# Sonar.net
KiCad netlist of a schematic drawn in Altium Designer
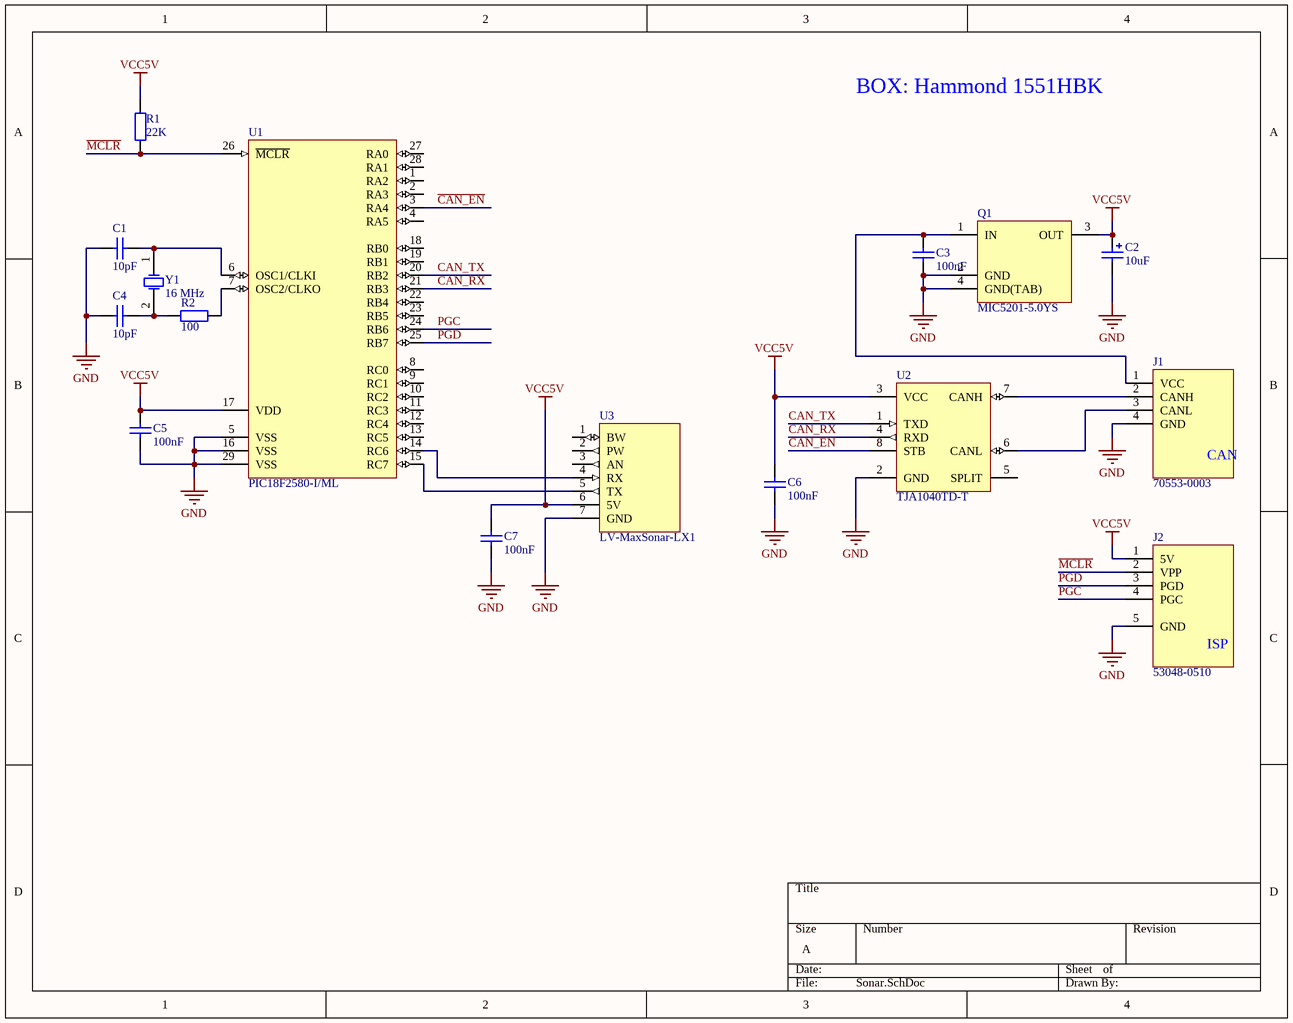
[diagram p0: Sonar.SchDoc]

(export (version "E")
  (design (tool "Eeschema 10.0.6"))
  (components
    (comp (ref "C1")
      (value "10pF")
      (footprint "CC1608-0603")
      (description "Capacitor")
      (fields (field (name "MANUFACTURER") "Panasonic") (field (name "Comment") "Cap"))
      (libsource (lib "Comp") (part "Cap"))
    )
    (comp (ref "C2")
      (value "10uF")
      (footprint "TC3528-1411")
      (description "Polarized Capacitor (Surface Mount)")
      (fields (field (name "MANUFACTURER") "AVX") (field (name "Comment") "TPSB106K016R0800"))
      (libsource (lib "Comp") (part "Cap Pol"))
    )
    (comp (ref "C3")
      (value "100nF")
      (footprint "CC1608-0603")
      (description "Capacitor")
      (fields (field (name "MANUFACTURER") "Taiyo Yuden") (field (name "Comment") "UMK107BJ104KA-T"))
      (libsource (lib "Comp") (part "Cap"))
    )
    (comp (ref "C4")
      (value "10pF")
      (footprint "CC1608-0603")
      (description "Capacitor")
      (fields (field (name "MANUFACTURER") "Panasonic") (field (name "Comment") "Cap"))
      (libsource (lib "Comp") (part "Cap"))
    )
    (comp (ref "C5")
      (value "100nF")
      (footprint "CC1608-0603")
      (description "Capacitor")
      (fields (field (name "MANUFACTURER") "Taiyo Yuden") (field (name "Comment") "UMK107BJ104KA-T"))
      (libsource (lib "Comp") (part "Cap"))
    )
    (comp (ref "C6")
      (value "100nF")
      (footprint "CC1608-0603")
      (description "Capacitor")
      (fields (field (name "MANUFACTURER") "Taiyo Yuden") (field (name "Comment") "UMK107BJ104KA-T"))
      (libsource (lib "Comp") (part "Cap"))
    )
    (comp (ref "C7")
      (value "100nF")
      (footprint "CC1608-0603")
      (description "Capacitor")
      (fields (field (name "MANUFACTURER") "Taiyo Yuden") (field (name "Comment") "UMK107BJ104KA-T"))
      (libsource (lib "Comp") (part "Cap"))
    )
    (comp (ref "J1")
      (value "70553-0003")
      (footprint "CON_CAN_Device-4")
      (description "4 pin CAN Connector 2.54mm pitch")
      (fields (field (name "MANUFACTURER") "Molex"))
      (libsource (lib "Comp") (part "CON_CAN_DEVICE"))
    )
    (comp (ref "J2")
      (value "53048-0510")
      (footprint "CON_ISP_H")
      (description "6 pin header - 1.25mm pitch horizontal")
      (fields (field (name "MANUFACTURER") "Molex"))
      (libsource (lib "Comp") (part "CON_ISP_Header_5p_1.25mm_horizontal"))
    )
    (comp (ref "Q1")
      (value "MIC5201-5.0YS")
      (footprint "DSO-G3")
      (description "5V LDO 200mA")
      (fields (field (name "MANUFACTURER") "Micrel"))
      (libsource (lib "Comp") (part "MIC5201-5.0YS"))
    )
    (comp (ref "R1")
      (value "22K")
      (footprint "CR1608-0603")
      (description "Resistor")
      (fields (field (name "Comment") "Res"))
      (libsource (lib "Comp") (part "Res"))
    )
    (comp (ref "R2")
      (value "100")
      (footprint "CR1608-0603")
      (description "Resistor")
      (fields (field (name "Comment") "Res"))
      (libsource (lib "") (part "Res_1"))
    )
    (comp (ref "U1")
      (value "PIC18F2580-I/ML")
      (footprint "Footprints:QFN6X6-28")
      (description "8 bit CAN MCU")
      (fields (field (name "MANUFACTURER") "Microchip"))
      (libsource (lib "Comp") (part "PIC18F2580-I/ML"))
    )
    (comp (ref "U2")
      (value "TJA1040TD-T")
      (footprint "Small Outline (~1.27mm Pitch) - 6to20 Leads:SO-G8/E2.9")
      (description "5V CAN Transceiver")
      (fields (field (name "MANUFACTURER") "NXP"))
      (libsource (lib "Comp") (part "TJA1040TD-T"))
    )
    (comp (ref "U3")
      (value "LV-MaxSonar-LX1")
      (footprint "MaxSonar")
      (description "Maxbotix ultrasound range sensor")
      (fields (field (name "MANUFACTURER") "Maxbotix"))
      (libsource (lib "Comp") (part "MaxSonar_LX1"))
    )
    (comp (ref "Y1")
      (value "16 MHz")
      (footprint "Footprints:CS10")
      (description "Crystal Oscillator")
      (fields (field (name "MANUFACTURER") "Citizen") (field (name "Comment") "CS10-16.000MABJ-UT"))
      (libsource (lib "Comp") (part "CS10"))
    )
  )
  (nets
    (net (code "1") (name "/CAN_RX") (class "Default")
      (node (ref "U1") (pin "21") (pinfunction "RB3_21") (pintype "bidirectional"))
      (node (ref "U2") (pin "4") (pinfunction "RXD_4") (pintype "output"))
    )
    (net (code "2") (name "/CAN_TX") (class "Default")
      (node (ref "U1") (pin "20") (pinfunction "RB2_20") (pintype "bidirectional"))
      (node (ref "U2") (pin "1") (pinfunction "TXD_1") (pintype "input"))
    )
    (net (code "3") (name "/PGC") (class "Default")
      (node (ref "J2") (pin "4") (pinfunction "PGC_4") (pintype "passive"))
      (node (ref "U1") (pin "24") (pinfunction "RB6_24") (pintype "bidirectional"))
    )
    (net (code "4") (name "/PGD") (class "Default")
      (node (ref "J2") (pin "3") (pinfunction "PGD_3") (pintype "passive"))
      (node (ref "U1") (pin "25") (pinfunction "RB7_25") (pintype "bidirectional"))
    )
    (net (code "5") (name "/~{CAN_EN}") (class "Default")
      (node (ref "U1") (pin "3") (pinfunction "RA4_3") (pintype "bidirectional"))
      (node (ref "U2") (pin "8") (pinfunction "STB_8") (pintype "passive"))
    )
    (net (code "6") (name "/~{MCLR}") (class "Default")
      (node (ref "J2") (pin "2") (pinfunction "VPP_2") (pintype "passive"))
      (node (ref "R1") (pin "1") (pinfunction "1_1") (pintype "passive"))
      (node (ref "U1") (pin "26") (pinfunction "~{MCLR}_26") (pintype "input"))
    )
    (net (code "7") (name "GND") (class "Default")
      (node (ref "C1") (pin "1") (pinfunction "1_1") (pintype "passive"))
      (node (ref "C2") (pin "2") (pinfunction "2_2") (pintype "passive"))
      (node (ref "C3") (pin "2") (pinfunction "2_2") (pintype "passive"))
      (node (ref "C4") (pin "1") (pinfunction "1_1") (pintype "passive"))
      (node (ref "C5") (pin "2") (pinfunction "2_2") (pintype "passive"))
      (node (ref "C6") (pin "2") (pinfunction "2_2") (pintype "passive"))
      (node (ref "C7") (pin "2") (pinfunction "2_2") (pintype "passive"))
      (node (ref "J1") (pin "4") (pinfunction "GND_4") (pintype "passive"))
      (node (ref "J2") (pin "5") (pinfunction "GND_5") (pintype "passive"))
      (node (ref "Q1") (pin "2") (pinfunction "GND_2") (pintype "power_in"))
      (node (ref "Q1") (pin "4") (pinfunction "GND(TAB)_4") (pintype "power_in"))
      (node (ref "U1") (pin "16") (pinfunction "VSS_16") (pintype "power_in"))
      (node (ref "U1") (pin "29") (pinfunction "VSS_29") (pintype "power_in"))
      (node (ref "U1") (pin "5") (pinfunction "VSS_5") (pintype "power_in"))
      (node (ref "U2") (pin "2") (pinfunction "GND_2") (pintype "power_in"))
      (node (ref "U3") (pin "7") (pinfunction "GND_7") (pintype "power_in"))
    )
    (net (code "8") (name "Net-(J1-CANH)") (class "Default")
      (node (ref "J1") (pin "2") (pinfunction "CANH_2") (pintype "passive"))
      (node (ref "U2") (pin "7") (pinfunction "CANH_7") (pintype "bidirectional"))
    )
    (net (code "9") (name "Net-(J1-CANL)") (class "Default")
      (node (ref "J1") (pin "3") (pinfunction "CANL_3") (pintype "passive"))
      (node (ref "U2") (pin "6") (pinfunction "CANL_6") (pintype "bidirectional"))
    )
    (net (code "10") (name "Net-(J1-VCC)") (class "Default")
      (node (ref "C3") (pin "1") (pinfunction "1_1") (pintype "passive"))
      (node (ref "J1") (pin "1") (pinfunction "VCC_1") (pintype "passive"))
      (node (ref "Q1") (pin "1") (pinfunction "IN_1") (pintype "power_in"))
    )
    (net (code "11") (name "Net-(U1-OSC1{slash}CLKI)") (class "Default")
      (node (ref "C1") (pin "2") (pinfunction "2_2") (pintype "passive"))
      (node (ref "U1") (pin "6") (pinfunction "OSC1/CLKI_6") (pintype "bidirectional"))
      (node (ref "Y1") (pin "1") (pinfunction "OSC1_1") (pintype "passive"))
    )
    (net (code "12") (name "Net-(U1-OSC2{slash}CLKO)") (class "Default")
      (node (ref "R2") (pin "1") (pinfunction "1_1") (pintype "passive"))
      (node (ref "U1") (pin "7") (pinfunction "OSC2/CLKO_7") (pintype "bidirectional"))
    )
    (net (code "13") (name "Net-(U1-RC6)") (class "Default")
      (node (ref "U1") (pin "14") (pinfunction "RC6_14") (pintype "bidirectional"))
      (node (ref "U3") (pin "4") (pinfunction "RX_4") (pintype "input"))
    )
    (net (code "14") (name "Net-(U1-RC7)") (class "Default")
      (node (ref "U1") (pin "15") (pinfunction "RC7_15") (pintype "bidirectional"))
      (node (ref "U3") (pin "5") (pinfunction "TX_5") (pintype "output"))
    )
    (net (code "15") (name "Net-(Y1-OSC2)") (class "Default")
      (node (ref "C4") (pin "2") (pinfunction "2_2") (pintype "passive"))
      (node (ref "R2") (pin "2") (pinfunction "2_2") (pintype "passive"))
      (node (ref "Y1") (pin "2") (pinfunction "OSC2_2") (pintype "passive"))
    )
    (net (code "16") (name "VCC5V") (class "Default")
      (node (ref "C2") (pin "1") (pinfunction "1_1") (pintype "passive"))
      (node (ref "C5") (pin "1") (pinfunction "1_1") (pintype "passive"))
      (node (ref "C6") (pin "1") (pinfunction "1_1") (pintype "passive"))
      (node (ref "C7") (pin "1") (pinfunction "1_1") (pintype "passive"))
      (node (ref "J2") (pin "1") (pinfunction "5V_1") (pintype "passive"))
      (node (ref "Q1") (pin "3") (pinfunction "OUT_3") (pintype "passive"))
      (node (ref "R1") (pin "2") (pinfunction "2_2") (pintype "passive"))
      (node (ref "U1") (pin "17") (pinfunction "VDD_17") (pintype "power_in"))
      (node (ref "U2") (pin "3") (pinfunction "VCC_3") (pintype "power_in"))
      (node (ref "U3") (pin "6") (pinfunction "5V_6") (pintype "power_in"))
    )
    (net (code "17") (name "unconnected-(U1-RA0-Pad27)") (class "Default")
      (node (ref "U1") (pin "27") (pinfunction "RA0_27") (pintype "bidirectional"))
    )
    (net (code "18") (name "unconnected-(U1-RA1-Pad28)") (class "Default")
      (node (ref "U1") (pin "28") (pinfunction "RA1_28") (pintype "bidirectional"))
    )
    (net (code "19") (name "unconnected-(U1-RA2-Pad1)") (class "Default")
      (node (ref "U1") (pin "1") (pinfunction "RA2_1") (pintype "bidirectional"))
    )
    (net (code "20") (name "unconnected-(U1-RA3-Pad2)") (class "Default")
      (node (ref "U1") (pin "2") (pinfunction "RA3_2") (pintype "bidirectional"))
    )
    (net (code "21") (name "unconnected-(U1-RA5-Pad4)") (class "Default")
      (node (ref "U1") (pin "4") (pinfunction "RA5_4") (pintype "bidirectional"))
    )
    (net (code "22") (name "unconnected-(U1-RB0-Pad18)") (class "Default")
      (node (ref "U1") (pin "18") (pinfunction "RB0_18") (pintype "bidirectional"))
    )
    (net (code "23") (name "unconnected-(U1-RB1-Pad19)") (class "Default")
      (node (ref "U1") (pin "19") (pinfunction "RB1_19") (pintype "bidirectional"))
    )
    (net (code "24") (name "unconnected-(U1-RB4-Pad22)") (class "Default")
      (node (ref "U1") (pin "22") (pinfunction "RB4_22") (pintype "bidirectional"))
    )
    (net (code "25") (name "unconnected-(U1-RB5-Pad23)") (class "Default")
      (node (ref "U1") (pin "23") (pinfunction "RB5_23") (pintype "bidirectional"))
    )
    (net (code "26") (name "unconnected-(U1-RC0-Pad8)") (class "Default")
      (node (ref "U1") (pin "8") (pinfunction "RC0_8") (pintype "bidirectional"))
    )
    (net (code "27") (name "unconnected-(U1-RC1-Pad9)") (class "Default")
      (node (ref "U1") (pin "9") (pinfunction "RC1_9") (pintype "bidirectional"))
    )
    (net (code "28") (name "unconnected-(U1-RC2-Pad10)") (class "Default")
      (node (ref "U1") (pin "10") (pinfunction "RC2_10") (pintype "bidirectional"))
    )
    (net (code "29") (name "unconnected-(U1-RC3-Pad11)") (class "Default")
      (node (ref "U1") (pin "11") (pinfunction "RC3_11") (pintype "bidirectional"))
    )
    (net (code "30") (name "unconnected-(U1-RC4-Pad12)") (class "Default")
      (node (ref "U1") (pin "12") (pinfunction "RC4_12") (pintype "bidirectional"))
    )
    (net (code "31") (name "unconnected-(U1-RC5-Pad13)") (class "Default")
      (node (ref "U1") (pin "13") (pinfunction "RC5_13") (pintype "bidirectional"))
    )
    (net (code "32") (name "unconnected-(U2-SPLIT-Pad5)") (class "Default")
      (node (ref "U2") (pin "5") (pinfunction "SPLIT_5") (pintype "passive"))
    )
    (net (code "33") (name "unconnected-(U3-AN-Pad3)") (class "Default")
      (node (ref "U3") (pin "3") (pinfunction "AN_3") (pintype "output"))
    )
    (net (code "34") (name "unconnected-(U3-BW-Pad1)") (class "Default")
      (node (ref "U3") (pin "1") (pinfunction "BW_1") (pintype "bidirectional"))
    )
    (net (code "35") (name "unconnected-(U3-PW-Pad2)") (class "Default")
      (node (ref "U3") (pin "2") (pinfunction "PW_2") (pintype "output"))
    )
  )
)
